# IO_FMU_REV_2A.net
KiCad netlist of a schematic drawn in Altium Designer
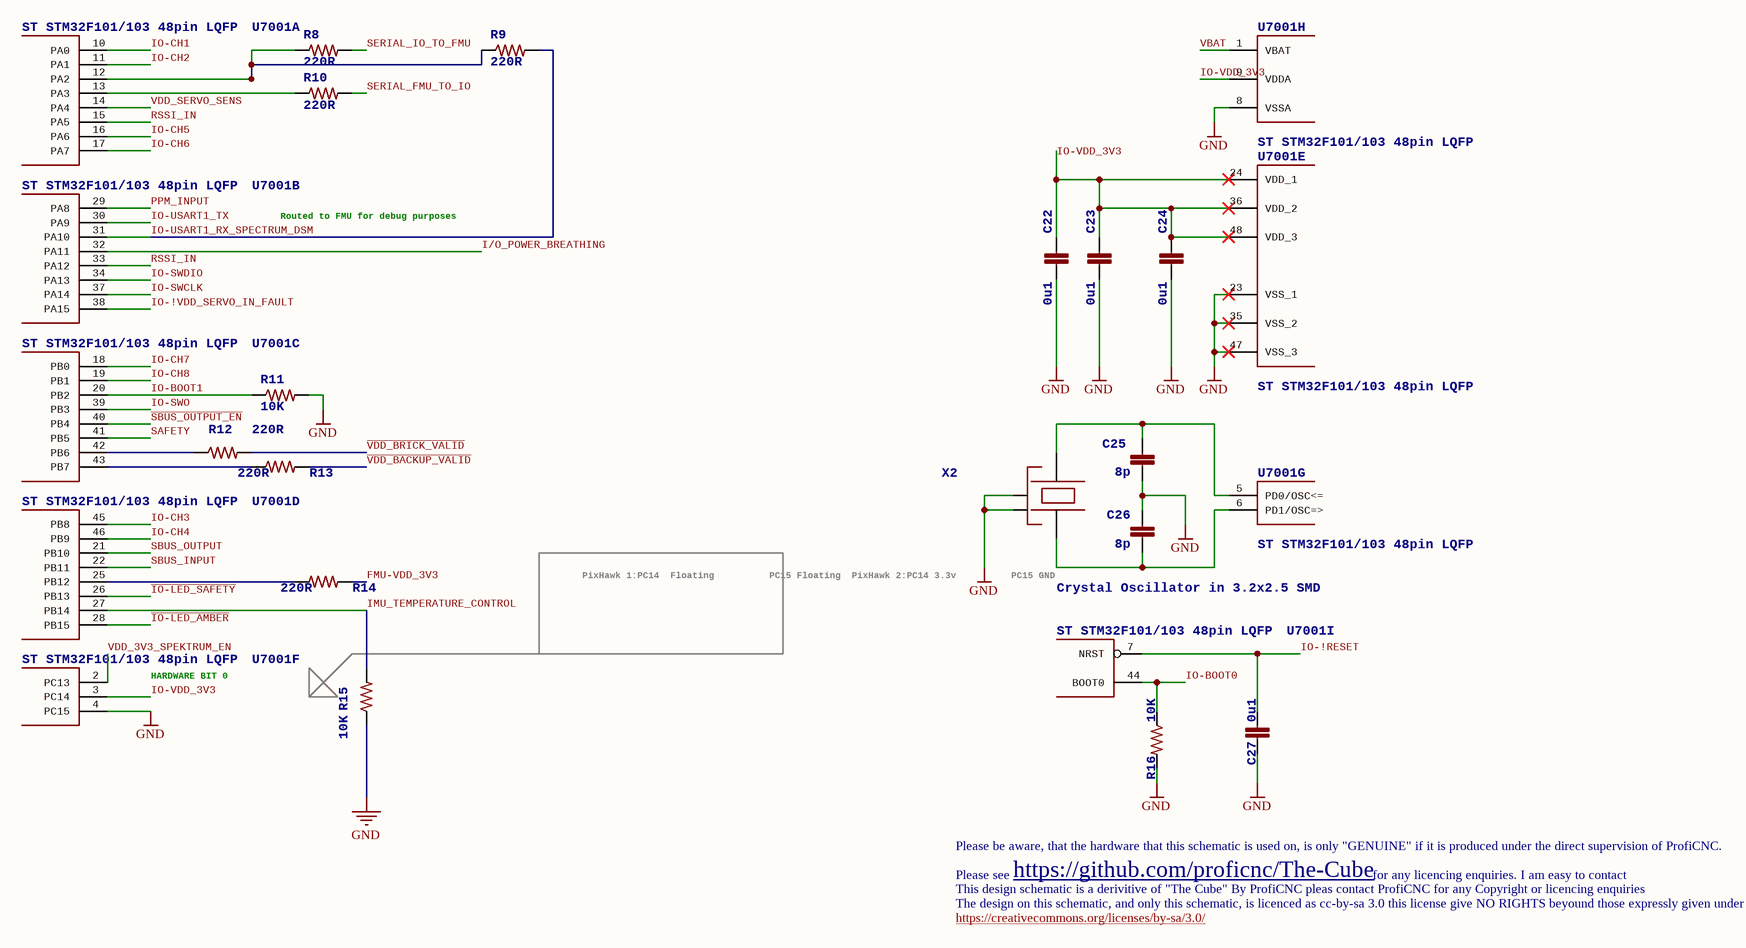
[diagram p0: IO_FMU_REV_2A.SchDoc]

(export (version "E")
  (design (tool "Eeschema 10.0.6"))
  (components
    (comp (ref "C22")
      (value "0u1")
      (footprint "0402-CAP")
      (description "CAP CER 0.1UF 16V Y5V 0402")
      (libsource (lib "") (part "CAP0402_1"))
    )
    (comp (ref "C23")
      (value "0u1")
      (footprint "0402-CAP")
      (description "CAP CER 0.1UF 16V Y5V 0402")
      (libsource (lib "") (part "CAP0402_1"))
    )
    (comp (ref "C24")
      (value "0u1")
      (footprint "0402-CAP")
      (description "CAP CER 0.1UF 16V Y5V 0402")
      (libsource (lib "") (part "CAP0402_1"))
    )
    (comp (ref "C25")
      (value "8p")
      (footprint "0402-CAP")
      (description "CAP CER 8PF 50V C0G 0402")
      (libsource (lib "") (part "CAP0402_1"))
    )
    (comp (ref "C26")
      (value "8p")
      (footprint "0402-CAP")
      (description "CAP CER 8PF 50V C0G 0402")
      (libsource (lib "") (part "CAP0402_1"))
    )
    (comp (ref "C27")
      (value "0u1")
      (footprint "0402-CAP")
      (description "CAP CER 0.1UF 16V Y5V 0402")
      (libsource (lib "pixhawk2") (part "CAP0402"))
    )
    (comp (ref "R8")
      (value "220R")
      (footprint "0402-RES")
      (description "RES 220 OHM 1/16W 1% 0402 SMD")
      (libsource (lib "pixhawk2") (part "RESISTOR0402-RES"))
    )
    (comp (ref "R9")
      (value "220R")
      (footprint "0402-RES")
      (description "RES 220 OHM 1/16W 1% 0402 SMD")
      (libsource (lib "pixhawk2") (part "RESISTOR0402-RES"))
    )
    (comp (ref "R10")
      (value "220R")
      (footprint "0402-RES")
      (description "RES 220 OHM 1/16W 1% 0402 SMD")
      (libsource (lib "pixhawk2") (part "RESISTOR0402-RES"))
    )
    (comp (ref "R11")
      (value "10K")
      (footprint "0402-RES")
      (description "RES 10K OHM 1/16W 1% 0402 SMD")
      (libsource (lib "pixhawk2") (part "RESISTOR0402-RES"))
    )
    (comp (ref "R12")
      (value "220R")
      (footprint "0402-RES")
      (description "RES 220 OHM 1/16W 1% 0402 SMD")
      (libsource (lib "pixhawk2") (part "RESISTOR0402-RES"))
    )
    (comp (ref "R13")
      (value "220R")
      (footprint "0402-RES")
      (description "RES 220 OHM 1/16W 1% 0402 SMD")
      (libsource (lib "pixhawk2") (part "RESISTOR0402-RES"))
    )
    (comp (ref "R14")
      (value "220R")
      (footprint "0402-RES")
      (description "RES 220 OHM 1/16W 1% 0402 SMD")
      (libsource (lib "pixhawk2") (part "RESISTOR0402-RES"))
    )
    (comp (ref "R15")
      (value "10K")
      (footprint "0402-RES")
      (description "RES 10K OHM 1/16W 1% 0402 SMD")
      (libsource (lib "pixhawk2") (part "RESISTOR0402-RES"))
    )
    (comp (ref "R16")
      (value "10K")
      (footprint "0402-RES")
      (description "RES 10K OHM 1/16W 1% 0402 SMD")
      (libsource (lib "pixhawk2") (part "RESISTOR0402-RES"))
    )
    (comp (ref "U7001")
      (value "ST STM32F101/103 48pin LQFP")
      (footprint "TQFP48")
      (description "MCU 32BIT ARM 64K FLASH 48LQFP")
      (libsource (lib "pixhawk2") (part "STM32F10XCXT6"))
    )
    (comp (ref "X2")
      (value "Crystal Oscillator in 3.2x2.5 SMD")
      (footprint "OSCILLATOR-3.2X2.5")
      (description "CRYSTAL 24MHZ 8PF SMD")
      (libsource (lib "pixhawk2") (part "OSCILLATOR-3.2X2.5"))
    )
  )
  (nets
    (net (code "1") (name "/FMU-VDD_3V3") (class "Default")
      (node (ref "R14") (pin "P$2") (pinfunction "2_P$2") (pintype "passive"))
    )
    (net (code "2") (name "/IMU_TEMPERATURE_CONTROL") (class "Default")
      (node (ref "R15") (pin "P$2") (pinfunction "2_P$2") (pintype "passive"))
      (node (ref "U7001") (pin "27") (pinfunction "PB14_27") (pintype "passive"))
    )
    (net (code "3") (name "/IO-!RESET") (class "Default")
      (node (ref "C27") (pin "P$2") (pinfunction "2_P$2") (pintype "passive"))
      (node (ref "U7001") (pin "7") (pinfunction "NRST_7") (pintype "passive"))
    )
    (net (code "4") (name "/IO-!VDD_SERVO_IN_FAULT") (class "Default")
      (node (ref "U7001") (pin "38") (pinfunction "PA15_38") (pintype "passive"))
    )
    (net (code "5") (name "/IO-BOOT0") (class "Default")
      (node (ref "R16") (pin "P$1") (pinfunction "1_P$1") (pintype "passive"))
      (node (ref "U7001") (pin "44") (pinfunction "BOOT0_44") (pintype "passive"))
    )
    (net (code "6") (name "/IO-BOOT1") (class "Default")
      (node (ref "R11") (pin "P$1") (pinfunction "1_P$1") (pintype "passive"))
      (node (ref "U7001") (pin "20") (pinfunction "PB2_20") (pintype "passive"))
    )
    (net (code "7") (name "/IO-CH1") (class "Default")
      (node (ref "U7001") (pin "10") (pinfunction "PA0_10") (pintype "passive"))
    )
    (net (code "8") (name "/IO-CH2") (class "Default")
      (node (ref "U7001") (pin "11") (pinfunction "PA1_11") (pintype "passive"))
    )
    (net (code "9") (name "/IO-CH3") (class "Default")
      (node (ref "U7001") (pin "45") (pinfunction "PB8_45") (pintype "passive"))
    )
    (net (code "10") (name "/IO-CH4") (class "Default")
      (node (ref "U7001") (pin "46") (pinfunction "PB9_46") (pintype "passive"))
    )
    (net (code "11") (name "/IO-CH5") (class "Default")
      (node (ref "U7001") (pin "16") (pinfunction "PA6_16") (pintype "passive"))
    )
    (net (code "12") (name "/IO-CH6") (class "Default")
      (node (ref "U7001") (pin "17") (pinfunction "PA7_17") (pintype "passive"))
    )
    (net (code "13") (name "/IO-CH7") (class "Default")
      (node (ref "U7001") (pin "18") (pinfunction "PB0_18") (pintype "passive"))
    )
    (net (code "14") (name "/IO-CH8") (class "Default")
      (node (ref "U7001") (pin "19") (pinfunction "PB1_19") (pintype "passive"))
    )
    (net (code "15") (name "/IO-SWCLK") (class "Default")
      (node (ref "U7001") (pin "37") (pinfunction "PA14_37") (pintype "passive"))
    )
    (net (code "16") (name "/IO-SWDIO") (class "Default")
      (node (ref "U7001") (pin "34") (pinfunction "PA13_34") (pintype "passive"))
    )
    (net (code "17") (name "/IO-SWO") (class "Default")
      (node (ref "U7001") (pin "39") (pinfunction "PB3_39") (pintype "passive"))
    )
    (net (code "18") (name "/IO-USART1_RX_SPECTRUM_DSM") (class "Default")
      (node (ref "R9") (pin "P$2") (pinfunction "2_P$2") (pintype "passive"))
      (node (ref "U7001") (pin "31") (pinfunction "PA10_31") (pintype "passive"))
    )
    (net (code "19") (name "/IO-USART1_TX") (class "Default")
      (node (ref "U7001") (pin "30") (pinfunction "PA9_30") (pintype "passive"))
    )
    (net (code "20") (name "/IO-VDD_3V3") (class "Default")
      (node (ref "C22") (pin "P$1") (pinfunction "1_P$1") (pintype "passive"))
      (node (ref "C23") (pin "P$1") (pinfunction "1_P$1") (pintype "passive"))
      (node (ref "C24") (pin "P$1") (pinfunction "1_P$1") (pintype "passive"))
      (node (ref "U7001") (pin "24") (pinfunction "VDD_1_24") (pintype "power_in"))
      (node (ref "U7001") (pin "3") (pinfunction "PC14_3") (pintype "passive"))
      (node (ref "U7001") (pin "36") (pinfunction "VDD_2_36") (pintype "power_in"))
      (node (ref "U7001") (pin "48") (pinfunction "VDD_3_48") (pintype "power_in"))
      (node (ref "U7001") (pin "9") (pinfunction "VDDA_9") (pintype "power_in"))
    )
    (net (code "21") (name "/I{slash}O_POWER_BREATHING") (class "Default")
      (node (ref "U7001") (pin "32") (pinfunction "PA11_32") (pintype "passive"))
    )
    (net (code "22") (name "/PPM_INPUT") (class "Default")
      (node (ref "U7001") (pin "29") (pinfunction "PA8_29") (pintype "passive"))
    )
    (net (code "23") (name "/RSSI_IN") (class "Default")
      (node (ref "U7001") (pin "15") (pinfunction "PA5_15") (pintype "passive"))
      (node (ref "U7001") (pin "33") (pinfunction "PA12_33") (pintype "passive"))
    )
    (net (code "24") (name "/SAFETY") (class "Default")
      (node (ref "U7001") (pin "41") (pinfunction "PB5_41") (pintype "passive"))
    )
    (net (code "25") (name "/SBUS_INPUT") (class "Default")
      (node (ref "U7001") (pin "22") (pinfunction "PB11_22") (pintype "passive"))
    )
    (net (code "26") (name "/SBUS_OUTPUT") (class "Default")
      (node (ref "U7001") (pin "21") (pinfunction "PB10_21") (pintype "passive"))
    )
    (net (code "27") (name "/SERIAL_FMU_TO_IO") (class "Default")
      (node (ref "R10") (pin "P$2") (pinfunction "2_P$2") (pintype "passive"))
    )
    (net (code "28") (name "/SERIAL_IO_TO_FMU") (class "Default")
      (node (ref "R8") (pin "P$2") (pinfunction "2_P$2") (pintype "passive"))
    )
    (net (code "29") (name "/VBAT") (class "Default")
      (node (ref "U7001") (pin "1") (pinfunction "VBAT_1") (pintype "power_in"))
    )
    (net (code "30") (name "/VDD_3V3_SPEKTRUM_EN") (class "Default")
      (node (ref "U7001") (pin "2") (pinfunction "PC13_2") (pintype "passive"))
    )
    (net (code "31") (name "/VDD_SERVO_SENS") (class "Default")
      (node (ref "U7001") (pin "14") (pinfunction "PA4_14") (pintype "passive"))
    )
    (net (code "32") (name "/~{IO-LED_AMBER}") (class "Default")
      (node (ref "U7001") (pin "28") (pinfunction "PB15_28") (pintype "passive"))
    )
    (net (code "33") (name "/~{IO-LED_SAFETY}") (class "Default")
      (node (ref "U7001") (pin "26") (pinfunction "PB13_26") (pintype "passive"))
    )
    (net (code "34") (name "/~{SBUS_OUTPUT_EN}") (class "Default")
      (node (ref "U7001") (pin "40") (pinfunction "PB4_40") (pintype "passive"))
    )
    (net (code "35") (name "/~{VDD_BACKUP_VALID}") (class "Default")
      (node (ref "R13") (pin "P$2") (pinfunction "2_P$2") (pintype "passive"))
    )
    (net (code "36") (name "/~{VDD_BRICK_VALID}") (class "Default")
      (node (ref "R12") (pin "P$2") (pinfunction "2_P$2") (pintype "passive"))
    )
    (net (code "37") (name "GND") (class "Default")
      (node (ref "C22") (pin "P$2") (pinfunction "2_P$2") (pintype "passive"))
      (node (ref "C23") (pin "P$2") (pinfunction "2_P$2") (pintype "passive"))
      (node (ref "C24") (pin "P$2") (pinfunction "2_P$2") (pintype "passive"))
      (node (ref "C25") (pin "P$2") (pinfunction "2_P$2") (pintype "passive"))
      (node (ref "C26") (pin "P$1") (pinfunction "1_P$1") (pintype "passive"))
      (node (ref "C27") (pin "P$1") (pinfunction "1_P$1") (pintype "passive"))
      (node (ref "R11") (pin "P$2") (pinfunction "2_P$2") (pintype "passive"))
      (node (ref "R15") (pin "P$1") (pinfunction "1_P$1") (pintype "passive"))
      (node (ref "R16") (pin "P$2") (pinfunction "2_P$2") (pintype "passive"))
      (node (ref "U7001") (pin "23") (pinfunction "VSS_1_23") (pintype "power_in"))
      (node (ref "U7001") (pin "35") (pinfunction "VSS_2_35") (pintype "power_in"))
      (node (ref "U7001") (pin "4") (pinfunction "PC15_4") (pintype "passive"))
      (node (ref "U7001") (pin "47") (pinfunction "VSS_3_47") (pintype "power_in"))
      (node (ref "U7001") (pin "8") (pinfunction "VSSA_8") (pintype "power_in"))
      (node (ref "X2") (pin "2") (pinfunction "NC_2_2") (pintype "open_emitter"))
      (node (ref "X2") (pin "4") (pinfunction "NC_4_4") (pintype "open_emitter"))
    )
    (net (code "38") (name "Net-(C25-1)") (class "Default")
      (node (ref "C25") (pin "P$1") (pinfunction "1_P$1") (pintype "passive"))
      (node (ref "U7001") (pin "5") (pinfunction "PD0/OSC<=_5") (pintype "passive"))
      (node (ref "X2") (pin "3") (pinfunction "3_3") (pintype "passive"))
    )
    (net (code "39") (name "Net-(C26-2)") (class "Default")
      (node (ref "C26") (pin "P$2") (pinfunction "2_P$2") (pintype "passive"))
      (node (ref "U7001") (pin "6") (pinfunction "PD1/OSC=>_6") (pintype "passive"))
      (node (ref "X2") (pin "1") (pinfunction "1_1") (pintype "passive"))
    )
    (net (code "40") (name "Net-(R8-1)") (class "Default")
      (node (ref "R8") (pin "P$1") (pinfunction "1_P$1") (pintype "passive"))
      (node (ref "R9") (pin "P$1") (pinfunction "1_P$1") (pintype "passive"))
      (node (ref "U7001") (pin "12") (pinfunction "PA2_12") (pintype "passive"))
    )
    (net (code "41") (name "Net-(R10-1)") (class "Default")
      (node (ref "R10") (pin "P$1") (pinfunction "1_P$1") (pintype "passive"))
      (node (ref "U7001") (pin "13") (pinfunction "PA3_13") (pintype "passive"))
    )
    (net (code "42") (name "Net-(R12-1)") (class "Default")
      (node (ref "R12") (pin "P$1") (pinfunction "1_P$1") (pintype "passive"))
      (node (ref "U7001") (pin "42") (pinfunction "PB6_42") (pintype "passive"))
    )
    (net (code "43") (name "Net-(R13-1)") (class "Default")
      (node (ref "R13") (pin "P$1") (pinfunction "1_P$1") (pintype "passive"))
      (node (ref "U7001") (pin "43") (pinfunction "PB7_43") (pintype "passive"))
    )
    (net (code "44") (name "Net-(R14-1)") (class "Default")
      (node (ref "R14") (pin "P$1") (pinfunction "1_P$1") (pintype "passive"))
      (node (ref "U7001") (pin "25") (pinfunction "PB12_25") (pintype "passive"))
    )
  )
)
